# 05_MCU_STM32F4_Interface.net
KiCad netlist of a schematic drawn in Altium Designer
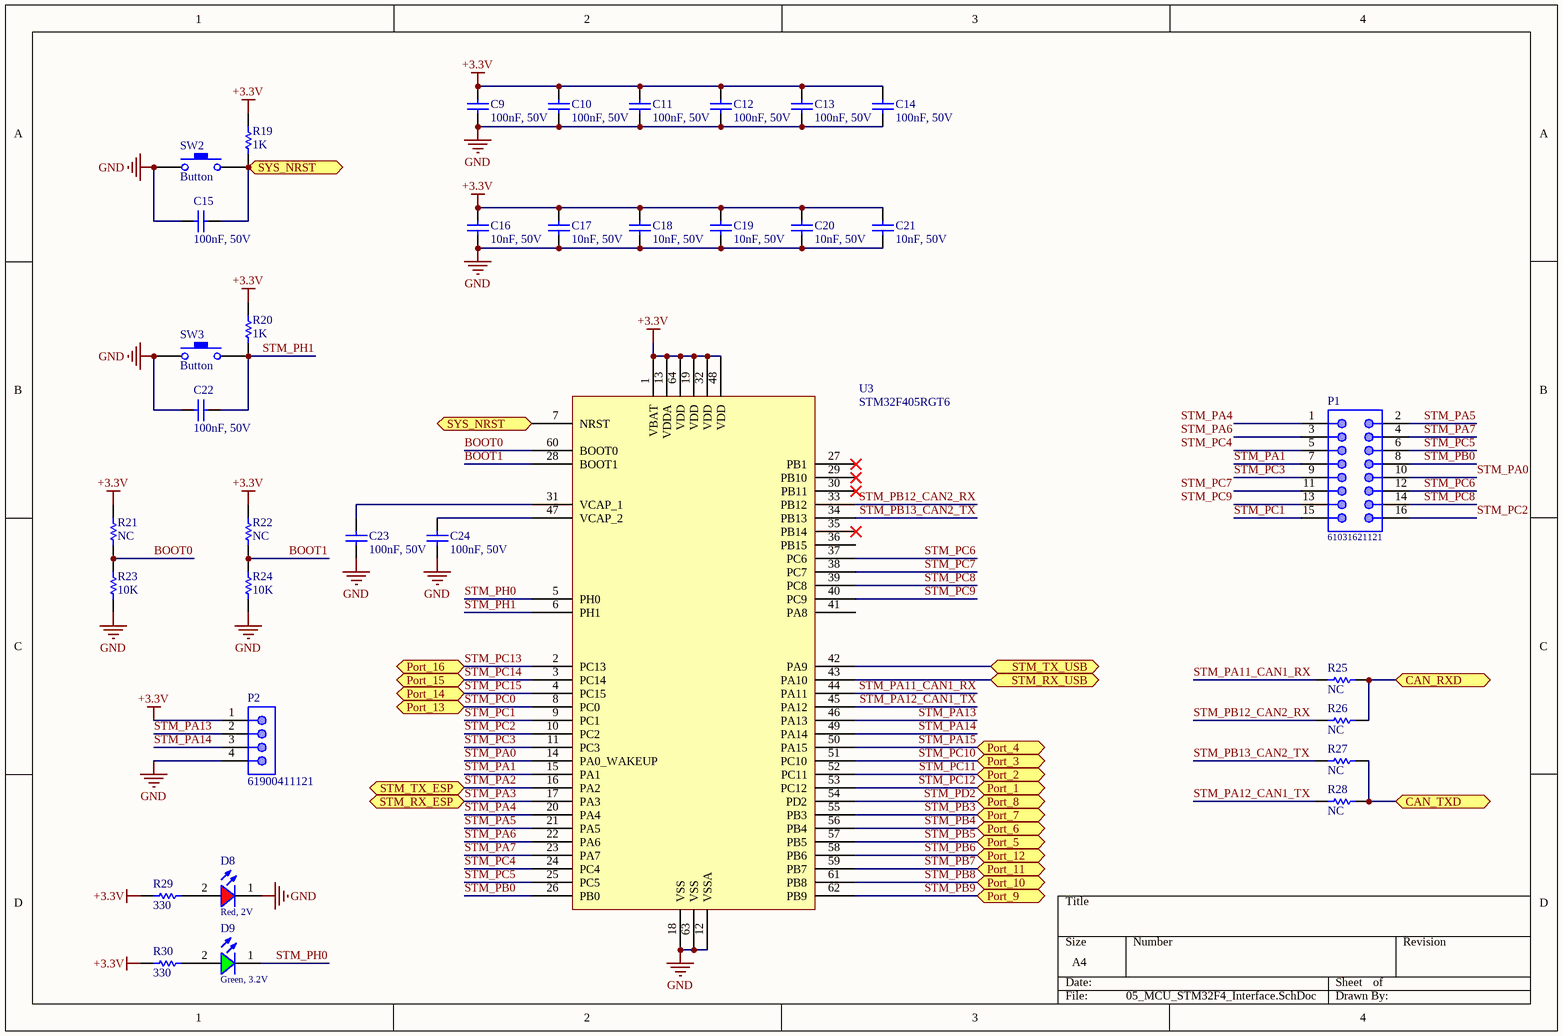
[diagram p0: 05_MCU_STM32F4_Interface.SchDoc]

(export (version "E")
  (design (tool "Eeschema 10.0.6"))
  (components
    (comp (ref "C9")
      (value "100nF, 50V")
      (footprint "WCAP-CSGP_0603_H=0.8mm_Reflow")
      (description "WCAP-CSGP Multilayer Ceramic Chip Capacitor, General Purpose, size 0603, X7R, 100nF, 50V")
      (fields
        (field (name "MANUFACTURER PART NUMBER") "885012206095")
        (field (name "MANUFACTURER") "Wurth Elektronik")
      )
      (libsource (lib "Altium_WCAP-CSGP (rev20a)") (part "885012206095"))
    )
    (comp (ref "C10")
      (value "100nF, 50V")
      (footprint "WCAP-CSGP_0603_H=0.8mm_Reflow")
      (description "WCAP-CSGP Multilayer Ceramic Chip Capacitor, General Purpose, size 0603, X7R, 100nF, 50V")
      (fields
        (field (name "MANUFACTURER PART NUMBER") "885012206095")
        (field (name "MANUFACTURER") "Wurth Elektronik")
      )
      (libsource (lib "Altium_WCAP-CSGP (rev20a)") (part "885012206095"))
    )
    (comp (ref "C11")
      (value "100nF, 50V")
      (footprint "WCAP-CSGP_0603_H=0.8mm_Reflow")
      (description "WCAP-CSGP Multilayer Ceramic Chip Capacitor, General Purpose, size 0603, X7R, 100nF, 50V")
      (fields
        (field (name "MANUFACTURER PART NUMBER") "885012206095")
        (field (name "MANUFACTURER") "Wurth Elektronik")
      )
      (libsource (lib "Altium_WCAP-CSGP (rev20a)") (part "885012206095"))
    )
    (comp (ref "C12")
      (value "100nF, 50V")
      (footprint "WCAP-CSGP_0603_H=0.8mm_Reflow")
      (description "WCAP-CSGP Multilayer Ceramic Chip Capacitor, General Purpose, size 0603, X7R, 100nF, 50V")
      (fields
        (field (name "MANUFACTURER PART NUMBER") "885012206095")
        (field (name "MANUFACTURER") "Wurth Elektronik")
      )
      (libsource (lib "Altium_WCAP-CSGP (rev20a)") (part "885012206095"))
    )
    (comp (ref "C13")
      (value "100nF, 50V")
      (footprint "WCAP-CSGP_0603_H=0.8mm_Reflow")
      (description "WCAP-CSGP Multilayer Ceramic Chip Capacitor, General Purpose, size 0603, X7R, 100nF, 50V")
      (fields
        (field (name "MANUFACTURER PART NUMBER") "885012206095")
        (field (name "MANUFACTURER") "Wurth Elektronik")
      )
      (libsource (lib "Altium_WCAP-CSGP (rev20a)") (part "885012206095"))
    )
    (comp (ref "C14")
      (value "100nF, 50V")
      (footprint "WCAP-CSGP_0603_H=0.8mm_Reflow")
      (description "WCAP-CSGP Multilayer Ceramic Chip Capacitor, General Purpose, size 0603, X7R, 100nF, 50V")
      (fields
        (field (name "MANUFACTURER PART NUMBER") "885012206095")
        (field (name "MANUFACTURER") "Wurth Elektronik")
      )
      (libsource (lib "Altium_WCAP-CSGP (rev20a)") (part "885012206095"))
    )
    (comp (ref "C15")
      (value "100nF, 50V")
      (footprint "WCAP-CSGP_0603_H=0.8mm_Reflow")
      (description "WCAP-CSGP Multilayer Ceramic Chip Capacitor, General Purpose, size 0603, X7R, 100nF, 50V")
      (fields
        (field (name "MANUFACTURER PART NUMBER") "885012206095")
        (field (name "MANUFACTURER") "Wurth Elektronik")
      )
      (libsource (lib "Altium_WCAP-CSGP (rev20a)") (part "885012206095"))
    )
    (comp (ref "C16")
      (value "10nF, 50V")
      (footprint "WCAP-CSGP_0603_H=0.8mm_Reflow")
      (description "WCAP-CSGP Multilayer Ceramic Chip Capacitor, General Purpose, size 0603, X7R, 10nF, 50V")
      (fields
        (field (name "MANUFACTURER PART NUMBER") "885012206089")
        (field (name "MANUFACTURER") "Wurth Elektronik")
      )
      (libsource (lib "Altium_WCAP-CSGP (rev20a)") (part "885012206089"))
    )
    (comp (ref "C17")
      (value "10nF, 50V")
      (footprint "WCAP-CSGP_0603_H=0.8mm_Reflow")
      (description "WCAP-CSGP Multilayer Ceramic Chip Capacitor, General Purpose, size 0603, X7R, 10nF, 50V")
      (fields
        (field (name "MANUFACTURER PART NUMBER") "885012206089")
        (field (name "MANUFACTURER") "Wurth Elektronik")
      )
      (libsource (lib "Altium_WCAP-CSGP (rev20a)") (part "885012206089"))
    )
    (comp (ref "C18")
      (value "10nF, 50V")
      (footprint "WCAP-CSGP_0603_H=0.8mm_Reflow")
      (description "WCAP-CSGP Multilayer Ceramic Chip Capacitor, General Purpose, size 0603, X7R, 10nF, 50V")
      (fields
        (field (name "MANUFACTURER PART NUMBER") "885012206089")
        (field (name "MANUFACTURER") "Wurth Elektronik")
      )
      (libsource (lib "Altium_WCAP-CSGP (rev20a)") (part "885012206089"))
    )
    (comp (ref "C19")
      (value "10nF, 50V")
      (footprint "WCAP-CSGP_0603_H=0.8mm_Reflow")
      (description "WCAP-CSGP Multilayer Ceramic Chip Capacitor, General Purpose, size 0603, X7R, 10nF, 50V")
      (fields
        (field (name "MANUFACTURER PART NUMBER") "885012206089")
        (field (name "MANUFACTURER") "Wurth Elektronik")
      )
      (libsource (lib "Altium_WCAP-CSGP (rev20a)") (part "885012206089"))
    )
    (comp (ref "C20")
      (value "10nF, 50V")
      (footprint "WCAP-CSGP_0603_H=0.8mm_Reflow")
      (description "WCAP-CSGP Multilayer Ceramic Chip Capacitor, General Purpose, size 0603, X7R, 10nF, 50V")
      (fields
        (field (name "MANUFACTURER PART NUMBER") "885012206089")
        (field (name "MANUFACTURER") "Wurth Elektronik")
      )
      (libsource (lib "Altium_WCAP-CSGP (rev20a)") (part "885012206089"))
    )
    (comp (ref "C21")
      (value "10nF, 50V")
      (footprint "WCAP-CSGP_0603_H=0.8mm_Reflow")
      (description "WCAP-CSGP Multilayer Ceramic Chip Capacitor, General Purpose, size 0603, X7R, 10nF, 50V")
      (fields
        (field (name "MANUFACTURER PART NUMBER") "885012206089")
        (field (name "MANUFACTURER") "Wurth Elektronik")
      )
      (libsource (lib "Altium_WCAP-CSGP (rev20a)") (part "885012206089"))
    )
    (comp (ref "C22")
      (value "100nF, 50V")
      (footprint "WCAP-CSGP_0603_H=0.8mm_Reflow")
      (description "WCAP-CSGP Multilayer Ceramic Chip Capacitor, General Purpose, size 0603, X7R, 100nF, 50V")
      (fields
        (field (name "MANUFACTURER PART NUMBER") "885012206095")
        (field (name "MANUFACTURER") "Wurth Elektronik")
      )
      (libsource (lib "Altium_WCAP-CSGP (rev20a)") (part "885012206095"))
    )
    (comp (ref "C23")
      (value "100nF, 50V")
      (footprint "WCAP-CSGP_0603_H=0.8mm_Reflow")
      (description "WCAP-CSGP Multilayer Ceramic Chip Capacitor, General Purpose, size 0603, X7R, 100nF, 50V")
      (fields
        (field (name "MANUFACTURER PART NUMBER") "885012206095")
        (field (name "MANUFACTURER") "Wurth Elektronik")
      )
      (libsource (lib "Altium_WCAP-CSGP (rev20a)") (part "885012206095"))
    )
    (comp (ref "C24")
      (value "100nF, 50V")
      (footprint "WCAP-CSGP_0603_H=0.8mm_Reflow")
      (description "WCAP-CSGP Multilayer Ceramic Chip Capacitor, General Purpose, size 0603, X7R, 100nF, 50V")
      (fields
        (field (name "MANUFACTURER PART NUMBER") "885012206095")
        (field (name "MANUFACTURER") "Wurth Elektronik")
      )
      (libsource (lib "Altium_WCAP-CSGP (rev20a)") (part "885012206095"))
    )
    (comp (ref "D8")
      (value "Red, 2V")
      (footprint "WL-SMCW_0603_H=0.7mm")
      (description "WL-SMCW SMT Mono-color Chip LED Waterclear, size 0603, Red, 2V, 140deg")
      (fields (field (name "PART NUMBER") "150060RS75000") (field (name "PUBLISHER") "Wurth Elektronik"))
      (libsource (lib "Altium_WL-SMCW (rev20a)") (part "150060RS75000"))
    )
    (comp (ref "D9")
      (value "Green, 3.2V")
      (footprint "WL-SMCW_0603_H=0.7mm")
      (description "WL-SMCW SMT Mono-color Chip LED Waterclear, size 0603, Green, 3.2V, 140deg")
      (fields (field (name "PART NUMBER") "150060GS75000") (field (name "PUBLISHER") "Wurth Elektronik"))
      (libsource (lib "Altium_WL-SMCW (rev20a)") (part "150060GS75000"))
    )
    (comp (ref "P1")
      (value "61031621121")
      (footprint "61031621121")
      (description "WR-PHD Pin Header, SMT, pitch 2.54mm, Dual Row, Vertical, 16p")
      (fields (field (name "MANUFACTURER") "Wurth Elektronik"))
      (libsource (lib "Altium_WR-PHD (rev20a)") (part "61031621121"))
    )
    (comp (ref "P2")
      (value "61900411121")
      (footprint "61900411121")
      (description "WR-WTB THT Male Vertical Locking Header, pitch 2.54mm, 4p")
      (fields (field (name "PUBLISHER") "Wurth Elektronik"))
      (libsource (lib "653008114822_Altium_WR-WTB_rev20a") (part "61900411121"))
    )
    (comp (ref "R19")
      (value "1K")
      (footprint "RES-SM-0603")
      (description "Resistor")
      (fields (field (name "Comment") "RESISTOR SMD"))
      (libsource (lib "PIF_Library") (part "RESISTOR SMD"))
    )
    (comp (ref "R20")
      (value "1K")
      (footprint "RES-SM-0603")
      (description "Resistor")
      (fields (field (name "Comment") "RESISTOR SMD"))
      (libsource (lib "PIF_Library") (part "RESISTOR SMD"))
    )
    (comp (ref "R21")
      (value "NC")
      (footprint "RES-SM-0603")
      (description "Resistor")
      (fields (field (name "Comment") "RESISTOR SMD"))
      (libsource (lib "PIF_Library") (part "RESISTOR SMD"))
    )
    (comp (ref "R22")
      (value "NC")
      (footprint "RES-SM-0603")
      (description "Resistor")
      (fields (field (name "Comment") "RESISTOR SMD"))
      (libsource (lib "PIF_Library") (part "RESISTOR SMD"))
    )
    (comp (ref "R23")
      (value "10K")
      (footprint "RES-SM-0603")
      (description "Resistor")
      (fields (field (name "Comment") "RESISTOR SMD"))
      (libsource (lib "PIF_Library") (part "RESISTOR SMD"))
    )
    (comp (ref "R24")
      (value "10K")
      (footprint "RES-SM-0603")
      (description "Resistor")
      (fields (field (name "Comment") "RESISTOR SMD"))
      (libsource (lib "PIF_Library") (part "RESISTOR SMD"))
    )
    (comp (ref "R25")
      (value "NC")
      (footprint "RES-SM-0603")
      (description "Resistor")
      (fields (field (name "Comment") "RESISTOR SMD"))
      (libsource (lib "PIF_Library") (part "RESISTOR SMD"))
    )
    (comp (ref "R26")
      (value "NC")
      (footprint "RES-SM-0603")
      (description "Resistor")
      (fields (field (name "Comment") "RESISTOR SMD"))
      (libsource (lib "PIF_Library") (part "RESISTOR SMD"))
    )
    (comp (ref "R27")
      (value "NC")
      (footprint "RES-SM-0603")
      (description "Resistor")
      (fields (field (name "Comment") "RESISTOR SMD"))
      (libsource (lib "PIF_Library") (part "RESISTOR SMD"))
    )
    (comp (ref "R28")
      (value "NC")
      (footprint "RES-SM-0603")
      (description "Resistor")
      (fields (field (name "Comment") "RESISTOR SMD"))
      (libsource (lib "PIF_Library") (part "RESISTOR SMD"))
    )
    (comp (ref "R29")
      (value "330")
      (footprint "RES-SM-0603")
      (description "Resistor")
      (fields (field (name "Comment") "RESISTOR SMD"))
      (libsource (lib "PIF_Library") (part "RESISTOR SMD"))
    )
    (comp (ref "R30")
      (value "330")
      (footprint "RES-SM-0603")
      (description "Resistor")
      (fields (field (name "Comment") "RESISTOR SMD"))
      (libsource (lib "PIF_Library") (part "RESISTOR SMD"))
    )
    (comp (ref "SW2")
      (value "Button")
      (footprint "Button 4-pin SMD")
      (libsource (lib "MiclsLib") (part "Button"))
    )
    (comp (ref "SW3")
      (value "Button")
      (footprint "Button 4-pin SMD")
      (libsource (lib "MiclsLib") (part "Button"))
    )
    (comp (ref "U3")
      (value "STM32F405RGT6")
      (footprint "CQFP50P1150X1150X160-64N")
      (fields (field (name "MANUFACTURER") "ST"))
      (libsource (lib "MiclsLib") (part "STM32F405RGT6"))
    )
  )
  (nets
    (net (code "1") (name "+3.3V") (class "Default")
      (node (ref "C10") (pin "2") (pinfunction "2_2") (pintype "passive"))
      (node (ref "C11") (pin "2") (pinfunction "2_2") (pintype "passive"))
      (node (ref "C12") (pin "2") (pinfunction "2_2") (pintype "passive"))
      (node (ref "C13") (pin "2") (pinfunction "2_2") (pintype "passive"))
      (node (ref "C14") (pin "2") (pinfunction "2_2") (pintype "passive"))
      (node (ref "C16") (pin "2") (pinfunction "2_2") (pintype "passive"))
      (node (ref "C17") (pin "2") (pinfunction "2_2") (pintype "passive"))
      (node (ref "C18") (pin "2") (pinfunction "2_2") (pintype "passive"))
      (node (ref "C19") (pin "2") (pinfunction "2_2") (pintype "passive"))
      (node (ref "C20") (pin "2") (pinfunction "2_2") (pintype "passive"))
      (node (ref "C21") (pin "2") (pinfunction "2_2") (pintype "passive"))
      (node (ref "C9") (pin "2") (pinfunction "2_2") (pintype "passive"))
      (node (ref "P2") (pin "1") (pinfunction "1_1") (pintype "passive"))
      (node (ref "R19") (pin "2") (pinfunction "2_2") (pintype "passive"))
      (node (ref "R20") (pin "2") (pinfunction "2_2") (pintype "passive"))
      (node (ref "R21") (pin "2") (pinfunction "2_2") (pintype "passive"))
      (node (ref "R22") (pin "2") (pinfunction "2_2") (pintype "passive"))
      (node (ref "R29") (pin "2") (pinfunction "2_2") (pintype "passive"))
      (node (ref "R30") (pin "2") (pinfunction "2_2") (pintype "passive"))
      (node (ref "U3") (pin "1") (pinfunction "VBAT_1") (pintype "passive"))
      (node (ref "U3") (pin "13") (pinfunction "VDDA_13") (pintype "passive"))
      (node (ref "U3") (pin "19") (pinfunction "VDD_19") (pintype "passive"))
      (node (ref "U3") (pin "32") (pinfunction "VDD_32") (pintype "passive"))
      (node (ref "U3") (pin "48") (pinfunction "VDD_48") (pintype "passive"))
      (node (ref "U3") (pin "64") (pinfunction "VDD_64") (pintype "passive"))
    )
    (net (code "2") (name "/BOOT0") (class "Default")
      (node (ref "R21") (pin "1") (pinfunction "1_1") (pintype "passive"))
      (node (ref "R23") (pin "2") (pinfunction "2_2") (pintype "passive"))
      (node (ref "U3") (pin "60") (pinfunction "BOOT0_60") (pintype "passive"))
    )
    (net (code "3") (name "/BOOT1") (class "Default")
      (node (ref "R22") (pin "1") (pinfunction "1_1") (pintype "passive"))
      (node (ref "R24") (pin "2") (pinfunction "2_2") (pintype "passive"))
      (node (ref "U3") (pin "28") (pinfunction "BOOT1_28") (pintype "passive"))
    )
    (net (code "4") (name "/CAN_RXD") (class "Default")
      (node (ref "R25") (pin "2") (pinfunction "2_2") (pintype "passive"))
      (node (ref "R26") (pin "2") (pinfunction "2_2") (pintype "passive"))
    )
    (net (code "5") (name "/CAN_TXD") (class "Default")
      (node (ref "R27") (pin "2") (pinfunction "2_2") (pintype "passive"))
      (node (ref "R28") (pin "2") (pinfunction "2_2") (pintype "passive"))
    )
    (net (code "6") (name "/STM_PA0") (class "Default")
      (node (ref "P1") (pin "10") (pinfunction "10_10") (pintype "passive"))
      (node (ref "U3") (pin "14") (pinfunction "PA0_WAKEUP_14") (pintype "passive"))
    )
    (net (code "7") (name "/STM_PA1") (class "Default")
      (node (ref "P1") (pin "7") (pinfunction "7_7") (pintype "passive"))
      (node (ref "U3") (pin "15") (pinfunction "PA1_15") (pintype "passive"))
    )
    (net (code "8") (name "/STM_PA2") (class "Default")
      (node (ref "U3") (pin "16") (pinfunction "PA2_16") (pintype "passive"))
    )
    (net (code "9") (name "/STM_PA3") (class "Default")
      (node (ref "U3") (pin "17") (pinfunction "PA3_17") (pintype "passive"))
    )
    (net (code "10") (name "/STM_PA4") (class "Default")
      (node (ref "P1") (pin "1") (pinfunction "1_1") (pintype "passive"))
      (node (ref "U3") (pin "20") (pinfunction "PA4_20") (pintype "passive"))
    )
    (net (code "11") (name "/STM_PA5") (class "Default")
      (node (ref "P1") (pin "2") (pinfunction "2_2") (pintype "passive"))
      (node (ref "U3") (pin "21") (pinfunction "PA5_21") (pintype "passive"))
    )
    (net (code "12") (name "/STM_PA6") (class "Default")
      (node (ref "P1") (pin "3") (pinfunction "3_3") (pintype "passive"))
      (node (ref "U3") (pin "22") (pinfunction "PA6_22") (pintype "passive"))
    )
    (net (code "13") (name "/STM_PA7") (class "Default")
      (node (ref "P1") (pin "4") (pinfunction "4_4") (pintype "passive"))
      (node (ref "U3") (pin "23") (pinfunction "PA7_23") (pintype "passive"))
    )
    (net (code "14") (name "/STM_PA11_CAN1_RX") (class "Default")
      (node (ref "R25") (pin "1") (pinfunction "1_1") (pintype "passive"))
      (node (ref "U3") (pin "44") (pinfunction "PA11_44") (pintype "passive"))
    )
    (net (code "15") (name "/STM_PA12_CAN1_TX") (class "Default")
      (node (ref "R28") (pin "1") (pinfunction "1_1") (pintype "passive"))
      (node (ref "U3") (pin "45") (pinfunction "PA12_45") (pintype "passive"))
    )
    (net (code "16") (name "/STM_PA13") (class "Default")
      (node (ref "P2") (pin "2") (pinfunction "2_2") (pintype "passive"))
      (node (ref "U3") (pin "46") (pinfunction "PA13_46") (pintype "passive"))
    )
    (net (code "17") (name "/STM_PA14") (class "Default")
      (node (ref "P2") (pin "3") (pinfunction "3_3") (pintype "passive"))
      (node (ref "U3") (pin "49") (pinfunction "PA14_49") (pintype "passive"))
    )
    (net (code "18") (name "/STM_PA15") (class "Default")
      (node (ref "U3") (pin "50") (pinfunction "PA15_50") (pintype "passive"))
    )
    (net (code "19") (name "/STM_PB0") (class "Default")
      (node (ref "P1") (pin "8") (pinfunction "8_8") (pintype "passive"))
      (node (ref "U3") (pin "26") (pinfunction "PB0_26") (pintype "passive"))
    )
    (net (code "20") (name "/STM_PB3") (class "Default")
      (node (ref "U3") (pin "55") (pinfunction "PB3_55") (pintype "passive"))
    )
    (net (code "21") (name "/STM_PB4") (class "Default")
      (node (ref "U3") (pin "56") (pinfunction "PB4_56") (pintype "passive"))
    )
    (net (code "22") (name "/STM_PB5") (class "Default")
      (node (ref "U3") (pin "57") (pinfunction "PB5_57") (pintype "passive"))
    )
    (net (code "23") (name "/STM_PB6") (class "Default")
      (node (ref "U3") (pin "58") (pinfunction "PB6_58") (pintype "passive"))
    )
    (net (code "24") (name "/STM_PB7") (class "Default")
      (node (ref "U3") (pin "59") (pinfunction "PB7_59") (pintype "passive"))
    )
    (net (code "25") (name "/STM_PB8") (class "Default")
      (node (ref "U3") (pin "61") (pinfunction "PB8_61") (pintype "passive"))
    )
    (net (code "26") (name "/STM_PB9") (class "Default")
      (node (ref "U3") (pin "62") (pinfunction "PB9_62") (pintype "passive"))
    )
    (net (code "27") (name "/STM_PB12_CAN2_RX") (class "Default")
      (node (ref "R26") (pin "1") (pinfunction "1_1") (pintype "passive"))
      (node (ref "U3") (pin "33") (pinfunction "PB12_33") (pintype "passive"))
    )
    (net (code "28") (name "/STM_PB13_CAN2_TX") (class "Default")
      (node (ref "R27") (pin "1") (pinfunction "1_1") (pintype "passive"))
      (node (ref "U3") (pin "34") (pinfunction "PB13_34") (pintype "passive"))
    )
    (net (code "29") (name "/STM_PC0") (class "Default")
      (node (ref "U3") (pin "8") (pinfunction "PC0_8") (pintype "passive"))
    )
    (net (code "30") (name "/STM_PC1") (class "Default")
      (node (ref "P1") (pin "15") (pinfunction "15_15") (pintype "passive"))
      (node (ref "U3") (pin "9") (pinfunction "PC1_9") (pintype "passive"))
    )
    (net (code "31") (name "/STM_PC2") (class "Default")
      (node (ref "P1") (pin "16") (pinfunction "16_16") (pintype "passive"))
      (node (ref "U3") (pin "10") (pinfunction "PC2_10") (pintype "passive"))
    )
    (net (code "32") (name "/STM_PC3") (class "Default")
      (node (ref "P1") (pin "9") (pinfunction "9_9") (pintype "passive"))
      (node (ref "U3") (pin "11") (pinfunction "PC3_11") (pintype "passive"))
    )
    (net (code "33") (name "/STM_PC4") (class "Default")
      (node (ref "P1") (pin "5") (pinfunction "5_5") (pintype "passive"))
      (node (ref "U3") (pin "24") (pinfunction "PC4_24") (pintype "passive"))
    )
    (net (code "34") (name "/STM_PC5") (class "Default")
      (node (ref "P1") (pin "6") (pinfunction "6_6") (pintype "passive"))
      (node (ref "U3") (pin "25") (pinfunction "PC5_25") (pintype "passive"))
    )
    (net (code "35") (name "/STM_PC6") (class "Default")
      (node (ref "P1") (pin "12") (pinfunction "12_12") (pintype "passive"))
      (node (ref "U3") (pin "37") (pinfunction "PC6_37") (pintype "passive"))
    )
    (net (code "36") (name "/STM_PC7") (class "Default")
      (node (ref "P1") (pin "11") (pinfunction "11_11") (pintype "passive"))
      (node (ref "U3") (pin "38") (pinfunction "PC7_38") (pintype "passive"))
    )
    (net (code "37") (name "/STM_PC8") (class "Default")
      (node (ref "P1") (pin "14") (pinfunction "14_14") (pintype "passive"))
      (node (ref "U3") (pin "39") (pinfunction "PC8_39") (pintype "passive"))
    )
    (net (code "38") (name "/STM_PC9") (class "Default")
      (node (ref "P1") (pin "13") (pinfunction "13_13") (pintype "passive"))
      (node (ref "U3") (pin "40") (pinfunction "PC9_40") (pintype "passive"))
    )
    (net (code "39") (name "/STM_PC10") (class "Default")
      (node (ref "U3") (pin "51") (pinfunction "PC10_51") (pintype "passive"))
    )
    (net (code "40") (name "/STM_PC11") (class "Default")
      (node (ref "U3") (pin "52") (pinfunction "PC11_52") (pintype "passive"))
    )
    (net (code "41") (name "/STM_PC12") (class "Default")
      (node (ref "U3") (pin "53") (pinfunction "PC12_53") (pintype "passive"))
    )
    (net (code "42") (name "/STM_PC13") (class "Default")
      (node (ref "U3") (pin "2") (pinfunction "PC13_2") (pintype "passive"))
    )
    (net (code "43") (name "/STM_PC14") (class "Default")
      (node (ref "U3") (pin "3") (pinfunction "PC14_3") (pintype "passive"))
    )
    (net (code "44") (name "/STM_PC15") (class "Default")
      (node (ref "U3") (pin "4") (pinfunction "PC15_4") (pintype "passive"))
    )
    (net (code "45") (name "/STM_PD2") (class "Default")
      (node (ref "U3") (pin "54") (pinfunction "PD2_54") (pintype "passive"))
    )
    (net (code "46") (name "/STM_PH0") (class "Default")
      (node (ref "D9") (pin "1") (pinfunction "K_1") (pintype "passive"))
      (node (ref "U3") (pin "5") (pinfunction "PH0_5") (pintype "passive"))
    )
    (net (code "47") (name "/STM_PH1") (class "Default")
      (node (ref "C22") (pin "2") (pinfunction "2_2") (pintype "passive"))
      (node (ref "R20") (pin "1") (pinfunction "1_1") (pintype "passive"))
      (node (ref "SW3") (pin "2") (pinfunction "8_2") (pintype "passive"))
      (node (ref "U3") (pin "6") (pinfunction "PH1_6") (pintype "passive"))
    )
    (net (code "48") (name "/STM_RX_USB") (class "Default")
      (node (ref "U3") (pin "43") (pinfunction "PA10_43") (pintype "passive"))
    )
    (net (code "49") (name "/STM_TX_USB") (class "Default")
      (node (ref "U3") (pin "42") (pinfunction "PA9_42") (pintype "passive"))
    )
    (net (code "50") (name "/SYS_NRST") (class "Default")
      (node (ref "C15") (pin "2") (pinfunction "2_2") (pintype "passive"))
      (node (ref "R19") (pin "1") (pinfunction "1_1") (pintype "passive"))
      (node (ref "SW2") (pin "2") (pinfunction "8_2") (pintype "passive"))
      (node (ref "U3") (pin "7") (pinfunction "NRST_7") (pintype "passive"))
    )
    (net (code "51") (name "GND") (class "Default")
      (node (ref "C10") (pin "1") (pinfunction "1_1") (pintype "passive"))
      (node (ref "C11") (pin "1") (pinfunction "1_1") (pintype "passive"))
      (node (ref "C12") (pin "1") (pinfunction "1_1") (pintype "passive"))
      (node (ref "C13") (pin "1") (pinfunction "1_1") (pintype "passive"))
      (node (ref "C14") (pin "1") (pinfunction "1_1") (pintype "passive"))
      (node (ref "C15") (pin "1") (pinfunction "1_1") (pintype "passive"))
      (node (ref "C16") (pin "1") (pinfunction "1_1") (pintype "passive"))
      (node (ref "C17") (pin "1") (pinfunction "1_1") (pintype "passive"))
      (node (ref "C18") (pin "1") (pinfunction "1_1") (pintype "passive"))
      (node (ref "C19") (pin "1") (pinfunction "1_1") (pintype "passive"))
      (node (ref "C20") (pin "1") (pinfunction "1_1") (pintype "passive"))
      (node (ref "C21") (pin "1") (pinfunction "1_1") (pintype "passive"))
      (node (ref "C22") (pin "1") (pinfunction "1_1") (pintype "passive"))
      (node (ref "C23") (pin "1") (pinfunction "1_1") (pintype "passive"))
      (node (ref "C24") (pin "1") (pinfunction "1_1") (pintype "passive"))
      (node (ref "C9") (pin "1") (pinfunction "1_1") (pintype "passive"))
      (node (ref "D8") (pin "1") (pinfunction "K_1") (pintype "passive"))
      (node (ref "P2") (pin "4") (pinfunction "4_4") (pintype "passive"))
      (node (ref "R23") (pin "1") (pinfunction "1_1") (pintype "passive"))
      (node (ref "R24") (pin "1") (pinfunction "1_1") (pintype "passive"))
      (node (ref "SW2") (pin "1") (pinfunction "7_1") (pintype "passive"))
      (node (ref "SW3") (pin "1") (pinfunction "7_1") (pintype "passive"))
      (node (ref "U3") (pin "12") (pinfunction "VSSA_12") (pintype "passive"))
      (node (ref "U3") (pin "18") (pinfunction "VSS_18") (pintype "passive"))
      (node (ref "U3") (pin "63") (pinfunction "VSS_63") (pintype "passive"))
    )
    (net (code "52") (name "Net-(D8-A)") (class "Default")
      (node (ref "D8") (pin "2") (pinfunction "A_2") (pintype "passive"))
      (node (ref "R29") (pin "1") (pinfunction "1_1") (pintype "passive"))
    )
    (net (code "53") (name "Net-(D9-A)") (class "Default")
      (node (ref "D9") (pin "2") (pinfunction "A_2") (pintype "passive"))
      (node (ref "R30") (pin "1") (pinfunction "1_1") (pintype "passive"))
    )
    (net (code "54") (name "Net-(U3-VCAP_1)") (class "Default")
      (node (ref "C23") (pin "2") (pinfunction "2_2") (pintype "passive"))
      (node (ref "U3") (pin "31") (pinfunction "VCAP_1_31") (pintype "passive"))
    )
    (net (code "55") (name "Net-(U3-VCAP_2)") (class "Default")
      (node (ref "C24") (pin "2") (pinfunction "2_2") (pintype "passive"))
      (node (ref "U3") (pin "47") (pinfunction "VCAP_2_47") (pintype "passive"))
    )
    (net (code "56") (name "unconnected-(U3-PA8-Pad41)") (class "Default")
      (node (ref "U3") (pin "41") (pinfunction "PA8_41") (pintype "passive"))
    )
    (net (code "57") (name "unconnected-(U3-PB1-Pad27)") (class "Default")
      (node (ref "U3") (pin "27") (pinfunction "PB1_27") (pintype "passive+no_connect"))
    )
    (net (code "58") (name "unconnected-(U3-PB10-Pad29)") (class "Default")
      (node (ref "U3") (pin "29") (pinfunction "PB10_29") (pintype "passive+no_connect"))
    )
    (net (code "59") (name "unconnected-(U3-PB11-Pad30)") (class "Default")
      (node (ref "U3") (pin "30") (pinfunction "PB11_30") (pintype "passive+no_connect"))
    )
    (net (code "60") (name "unconnected-(U3-PB14-Pad35)") (class "Default")
      (node (ref "U3") (pin "35") (pinfunction "PB14_35") (pintype "passive+no_connect"))
    )
    (net (code "61") (name "unconnected-(U3-PB15-Pad36)") (class "Default")
      (node (ref "U3") (pin "36") (pinfunction "PB15_36") (pintype "passive"))
    )
  )
)
